# Sheet1.net
KiCad netlist of a schematic drawn in Altium Designer
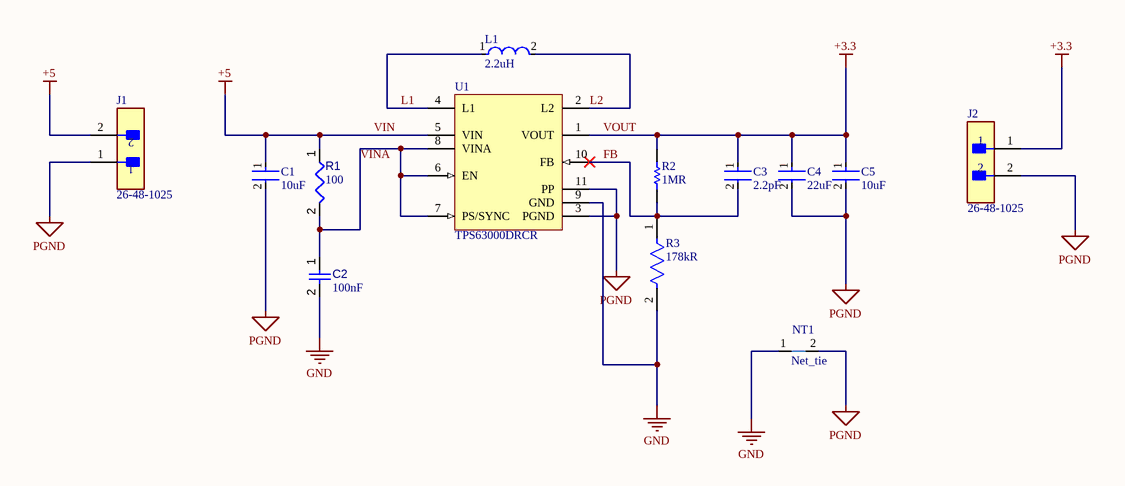
[diagram p0: Sheet1.SchDoc]

(export (version "E")
  (design (tool "Eeschema 10.0.6"))
  (components
    (comp (ref "C1")
      (value "10uF")
      (footprint "FP-CL10-IPC_B")
      (description "Ceramic capacitor SMD-0603 10uF /6.3V X5R# M +-20%, Samsung, RoHS")
      (fields (field (name "VOLTAGE") "6.3V") (field (name "TOLERANCE") "20%"))
      (libsource (lib "Ambivert_Roboticist") (part "b4654b650e69147ec39a6b967a45e02"))
    )
    (comp (ref "C2")
      (value "100nF")
      (footprint "CAPC1608X90X40NL10T20")
      (description "Chip Capacitor, 100 nF, +/- 10%, 50 V, 0603 (1608 Metric)")
      (fields (field (name "TOLERANCE") "10%") (field (name "Comment") "Capacitor 100 nF +/-10% 50 V 0603"))
      (libsource (lib "Ambivert_Roboticist") (part "CAP-NP-2"))
    )
    (comp (ref "C3")
      (value "2.2pF")
      (footprint "FP-C0603C-CF-IPC_B")
      (description "Ceramic Capacitor 2.2PF 50V, C0G, 0.25PF, 0603, Full Reel")
      (fields (field (name "VOLTAGE") "50V") (field (name "Comment") "C0603C229C5GACTU"))
      (libsource (lib "Ambivert_Roboticist") (part "b4654b650e69147ec39a6b967a45e02"))
    )
    (comp (ref "C4")
      (value "22uF")
      (footprint "FP-GRM188-0_2-IPC_C")
      (description "0603 22 uF 10 V ±20% Tolerance X5R Multilayer Ceramic Chip Capacitor")
      (fields (field (name "TOLERANCE") "20%") (field (name "Comment") "GRM188R61A226ME15D"))
      (libsource (lib "Ambivert_Roboticist") (part "11868f565c42a9108669ba33697ecf6"))
    )
    (comp (ref "C5")
      (value "10uF")
      (footprint "FP-CL10-IPC_B")
      (description "Ceramic capacitor SMD-0603 10uF /6.3V X5R# M +-20%, Samsung, RoHS")
      (fields (field (name "VOLTAGE") "6.3V") (field (name "TOLERANCE") "20%"))
      (libsource (lib "Ambivert_Roboticist") (part "b4654b650e69147ec39a6b967a45e02"))
    )
    (comp (ref "J1")
      (value "26-48-1025")
      (footprint "FP-26-48-1025-MFG")
      (description "KK 396 Breakaway Header, Vertical, Square Pin, with Friction Lock, 2 Circuits, Tin (Sn) Plating")
      (libsource (lib "") (part "3bc925449376181038e59eaffc5286c_1"))
    )
    (comp (ref "J2")
      (value "26-48-1025")
      (footprint "FP-26-48-1025-MFG")
      (description "KK 396 Breakaway Header, Vertical, Square Pin, with Friction Lock, 2 Circuits, Tin (Sn) Plating")
      (libsource (lib "Ambivert_Roboticist") (part "3bc925449376181038e59eaffc5286c"))
    )
    (comp (ref "L1")
      (value "2.2uH")
      (footprint "FP-LQH31CN_03-MFG")
      (description "Ind Power Chip Unshielded Wirewound 2.2uH 20% 1MHz Ferrite 430mA 1206 Embossed T/R")
      (fields (field (name "TOLERANCE") "20%") (field (name "Comment") "LQH31CN2R2M03L"))
      (libsource (lib "Ambivert_Roboticist") (part "725321dda6339637d4d059423bc1c3c"))
    )
    (comp (ref "NT1")
      (value "Net_tie")
      (footprint "Net_tie-Footprint-1")
      (libsource (lib "Ambivert_Roboticist") (part "Net_tie"))
    )
    (comp (ref "R1")
      (value "100")
      (footprint "RESC0402(1005)_L")
      (description "Chip Resistor, 100 Ohms, +/-1 %, 63 mW, -55 to 155 degC, 0402")
      (fields (field (name "POWER") "63mW") (field (name "TOLERANCE") "1%"))
      (libsource (lib "Ambivert_Roboticist") (part "RES-2"))
    )
    (comp (ref "R2")
      (value "1MR")
      (footprint "RESC1608X55X25LL10T15")
      (description "Res Thick Film 0603 1M Ohm 1% 1/10W ±100ppm/°C Molded SMD Paper T/R")
      (fields (field (name "TOLERANCE") "1%") (field (name "Comment") "RC0603FR-071ML"))
      (libsource (lib "") (part "RES-2_1"))
    )
    (comp (ref "R3")
      (value "178kR")
      (footprint "FP-RT0603-IPC_C")
      (description "Res Thin Film 0603 178K Ohm 0.5% 1/10W ±25ppm/°C Molded SMD Paper T/R")
      (fields (field (name "TOLERANCE") "0.5%") (field (name "Comment") "RT0603DRD07178KL"))
      (libsource (lib "Ambivert_Roboticist") (part "1029c3af85768c4190bb7ad29bc67b5"))
    )
    (comp (ref "U1")
      (value "TPS63000DRCR")
      (footprint "DRC0010J_V")
      (libsource (lib "Ambivert_Roboticist") (part "TI-TPS63000DRC10-3000X1650TP"))
    )
  )
  (nets
    (net (code "1") (name "+3.3") (class "Default")
      (node (ref "C3") (pin "1") (pinfunction "1_1") (pintype "passive"))
      (node (ref "C4") (pin "1") (pinfunction "1_1") (pintype "passive"))
      (node (ref "C5") (pin "1") (pinfunction "1_1") (pintype "passive"))
      (node (ref "J2") (pin "1") (pinfunction "1_1") (pintype "passive"))
      (node (ref "R2") (pin "2") (pinfunction "2_2") (pintype "passive"))
      (node (ref "U1") (pin "1") (pinfunction "VOUT_1") (pintype "power_in"))
    )
    (net (code "2") (name "+5") (class "Default")
      (node (ref "C1") (pin "1") (pinfunction "1_1") (pintype "passive"))
      (node (ref "J1") (pin "2") (pinfunction "2_2") (pintype "passive"))
      (node (ref "R1") (pin "1") (pinfunction "1_1") (pintype "passive"))
      (node (ref "U1") (pin "5") (pinfunction "VIN_5") (pintype "power_in"))
    )
    (net (code "3") (name "/FB") (class "Default")
      (node (ref "C3") (pin "2") (pinfunction "2_2") (pintype "passive"))
      (node (ref "R2") (pin "1") (pinfunction "1_1") (pintype "passive"))
      (node (ref "R3") (pin "1") (pinfunction "1_1") (pintype "passive"))
      (node (ref "U1") (pin "10") (pinfunction "FB_10") (pintype "input"))
    )
    (net (code "4") (name "/L1") (class "Default")
      (node (ref "L1") (pin "1") (pinfunction "1_1") (pintype "passive"))
      (node (ref "U1") (pin "4") (pinfunction "L1_4") (pintype "passive"))
    )
    (net (code "5") (name "/L2") (class "Default")
      (node (ref "L1") (pin "2") (pinfunction "2_2") (pintype "passive"))
      (node (ref "U1") (pin "2") (pinfunction "L2_2") (pintype "passive"))
    )
    (net (code "6") (name "/VINA") (class "Default")
      (node (ref "C2") (pin "1") (pinfunction "1_1") (pintype "passive"))
      (node (ref "R1") (pin "2") (pinfunction "2_2") (pintype "passive"))
      (node (ref "U1") (pin "6") (pinfunction "EN_6") (pintype "input"))
      (node (ref "U1") (pin "7") (pinfunction "PS/SYNC_7") (pintype "input"))
      (node (ref "U1") (pin "8") (pinfunction "VINA_8") (pintype "power_in"))
    )
    (net (code "7") (name "GND") (class "Default")
      (node (ref "C2") (pin "2") (pinfunction "2_2") (pintype "passive"))
      (node (ref "NT1") (pin "1") (pinfunction "1_1") (pintype "passive"))
      (node (ref "R3") (pin "2") (pinfunction "2_2") (pintype "passive"))
      (node (ref "U1") (pin "9") (pinfunction "GND_9") (pintype "power_in"))
    )
    (net (code "8") (name "PGND") (class "Default")
      (node (ref "C1") (pin "2") (pinfunction "2_2") (pintype "passive"))
      (node (ref "C4") (pin "2") (pinfunction "2_2") (pintype "passive"))
      (node (ref "C5") (pin "2") (pinfunction "2_2") (pintype "passive"))
      (node (ref "J1") (pin "1") (pinfunction "1_1") (pintype "passive"))
      (node (ref "J2") (pin "2") (pinfunction "2_2") (pintype "passive"))
      (node (ref "NT1") (pin "2") (pinfunction "2_2") (pintype "passive"))
      (node (ref "U1") (pin "11") (pinfunction "PP_11") (pintype "power_in"))
      (node (ref "U1") (pin "3") (pinfunction "PGND_3") (pintype "power_in"))
    )
  )
)
